# main.net
KiCad netlist of a schematic drawn in Altium Designer
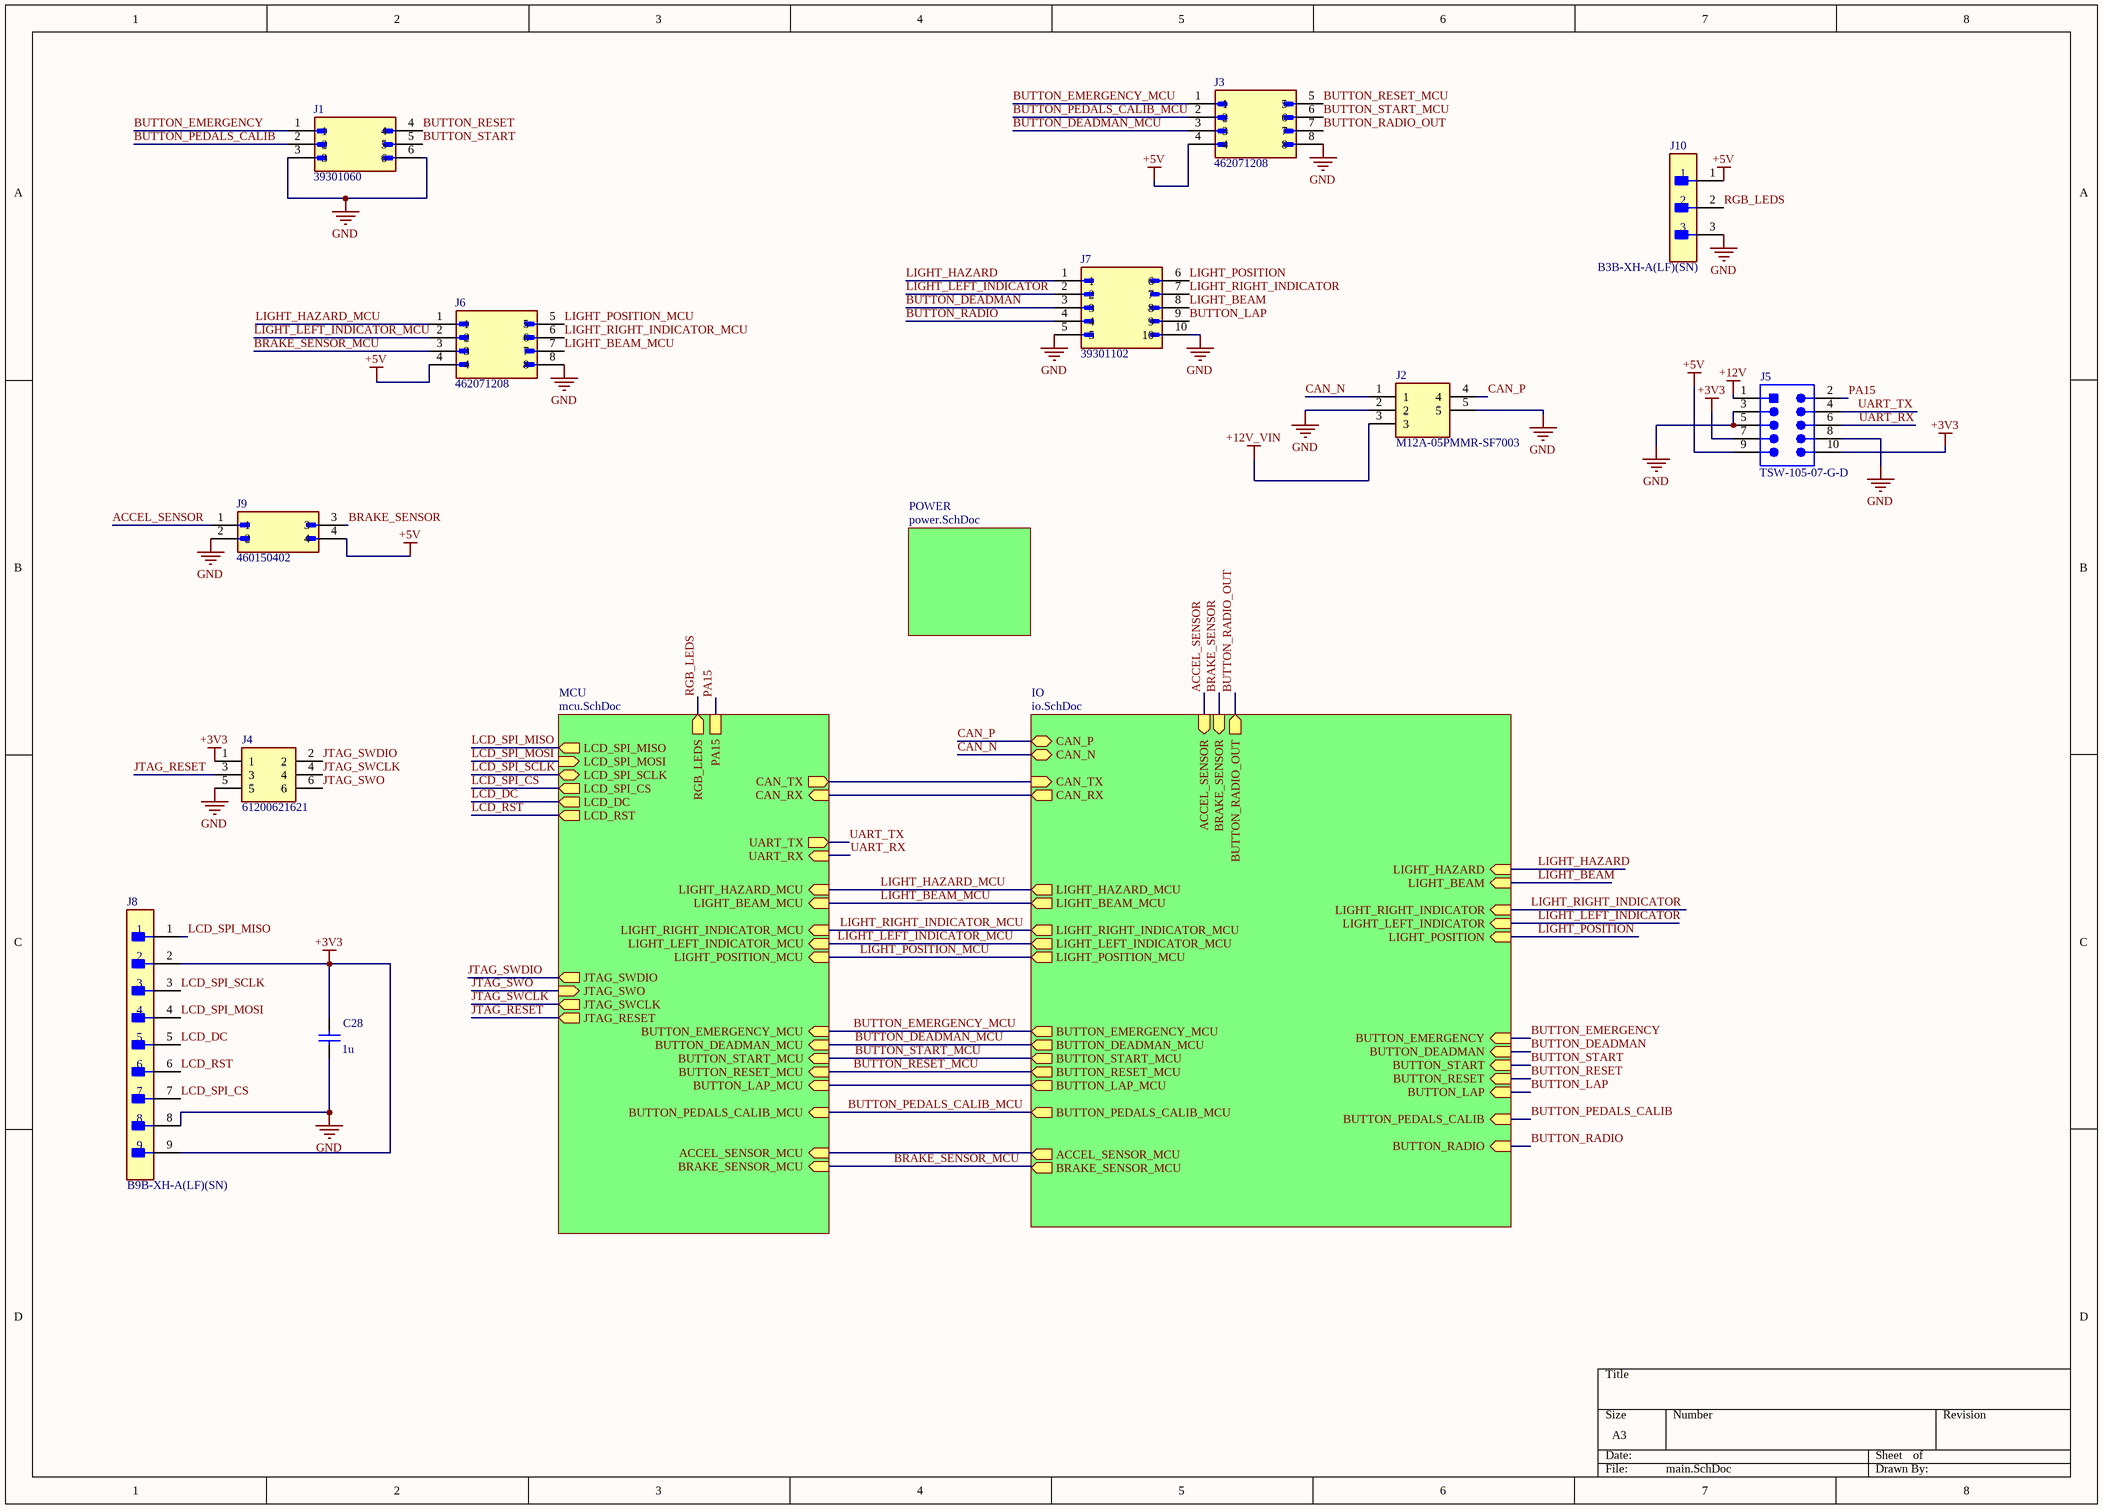
[diagram p0: main.SchDoc]

(export (version "E")
  (design (tool "Eeschema 10.0.6"))
  (components
    (comp (ref "C28")
      (value "1u")
      (footprint "CAPC1206(3216)150_L")
      (description "CAP 1.8uF 10V ±5% 1206 (3216 Metric) Thickness 1.45mm SMD")
      (fields (field (name "TOLERANCE") "Â±5%"))
      (libsource (lib "Altium Content Vault") (part "CAP"))
    )
    (comp (ref "J1")
      (value "39301060")
      (footprint "39301060")
      (description "Mini-Fit Jr. Through Hole PCB Header, Right Angle, 6 Contacts, 2 Rows, 4.2mm Pitch")
      (fields (field (name "MANUFACTURER") "Molex") (field (name "MANUFACTURER PART NUMBER") "39-30-1060"))
      (libsource (lib "HydrogreenLibrary") (part "39301060"))
    )
    (comp (ref "J2")
      (value "M12A-05PMMR-SF7003")
      (footprint "M12A05PMMRSF7003")
      (description "M12, A Code, 4A, 05 pins, Male Contact, Hexagonal, M12*1.0, PCB 90ø, Front Fastened, IP67")
      (fields
        (field (name "MOUSER PART NUMBER") "523-M12A05PMMRSF7003")
        (field (name "MANUFACTURER") "Amphenol LTW")
      )
      (libsource (lib "HydrogreenLibrary") (part "M12A-05PMMR-SF7003"))
    )
    (comp (ref "J3")
      (value "462071208")
      (footprint "462071208")
      (description "Mini-Fit Jr 46207 ROHS3Compliant Tin Solder Connector Header 100.0muin 2.54mum")
      (fields (field (name "MANUFACTURER") "Molex") (field (name "MANUFACTURER PART NUMBER") "46207-1208"))
      (libsource (lib "HydrogreenLibrary") (part "462071208"))
    )
    (comp (ref "J4")
      (value "61200621621")
      (footprint "61200621621")
      (description "Conn Shrouded Header (4 Sides) M 6 POS 2.54mm Solder ST Top Entry Thru-Hole Tray")
      (fields
        (field (name "MOUSER PART NUMBER") "710-61200621621")
        (field (name "MANUFACTURER") "Wurth Elektronik")
      )
      (libsource (lib "HydrogreenLibrary") (part "61200621621"))
    )
    (comp (ref "J5")
      (value "TSW-105-07-G-D")
      (footprint "SMTC-TSW-105-07-G-D_V")
      (fields (field (name "MANUFACTURER") "Samtec-Inc."))
      (libsource (lib "Altium Content Vault") (part "CN-2P-M-R10"))
    )
    (comp (ref "J6")
      (value "462071208")
      (footprint "462071208")
      (description "Mini-Fit Jr 46207 ROHS3Compliant Tin Solder Connector Header 100.0muin 2.54mum")
      (fields (field (name "MANUFACTURER") "Molex") (field (name "MANUFACTURER PART NUMBER") "46207-1208"))
      (libsource (lib "HydrogreenLibrary") (part "462071208"))
    )
    (comp (ref "J7")
      (value "39301102")
      (footprint "39301102")
      (libsource (lib "HydrogreenLibrary") (part "39301102"))
    )
    (comp (ref "J8")
      (value "B9B-XH-A(LF)(SN)")
      (footprint "FP-B9B-XH-A_LF_SN-MFG")
      (description "CONN HEADER VERT 9POS 2.5MM")
      (libsource (lib "Altium Content Vault") (part "dac6df820644cf490af5575b4ac23d9"))
    )
    (comp (ref "J9")
      (value "460150402")
      (footprint "460150402")
      (description "vert header, DR, 4w, tin, UL94V-0 ¦ Molex Incorporated 46015-0402")
      (fields (field (name "MF") "Molex") (field (name "MP") "46015-0402"))
      (libsource (lib "HydrogreenLibrary") (part "460150402"))
    )
    (comp (ref "J10")
      (value "B3B-XH-A(LF)(SN)")
      (footprint "FP-B3B-XH-A_LF_SN-MFG")
      (description "CONN HEADER VERT 3POS 2.5MM")
      (libsource (lib "Altium Content Vault") (part "0d3f023dd272f625e17a2be33dea85f"))
    )
  )
  (nets
    (net (code "1") (name "+3V3") (class "Default")
      (node (ref "C28") (pin "1") (pinfunction "1_1") (pintype "passive"))
      (node (ref "J4") (pin "1") (pinfunction "1_1") (pintype "passive"))
      (node (ref "J5") (pin "10") (pinfunction "10_10") (pintype "passive"))
      (node (ref "J5") (pin "7") (pinfunction "7_7") (pintype "passive"))
      (node (ref "J8") (pin "2") (pinfunction "2_2") (pintype "passive"))
      (node (ref "J8") (pin "9") (pinfunction "9_9") (pintype "passive"))
    )
    (net (code "2") (name "+5V") (class "Default")
      (node (ref "J10") (pin "1") (pinfunction "1_1") (pintype "passive"))
      (node (ref "J3") (pin "4") (pinfunction "4_4") (pintype "passive"))
      (node (ref "J5") (pin "9") (pinfunction "9_9") (pintype "passive"))
      (node (ref "J6") (pin "4") (pinfunction "4_4") (pintype "passive"))
      (node (ref "J9") (pin "4") (pinfunction "4_4") (pintype "passive"))
    )
    (net (code "3") (name "+12V") (class "Default")
      (node (ref "J5") (pin "1") (pinfunction "1_1") (pintype "passive"))
    )
    (net (code "4") (name "+12V_VIN") (class "Default")
      (node (ref "J2") (pin "3") (pinfunction "3_3") (pintype "passive"))
    )
    (net (code "5") (name "/ACCEL_SENSOR") (class "Default")
      (node (ref "J9") (pin "1") (pinfunction "1_1") (pintype "passive"))
    )
    (net (code "7") (name "/BRAKE_SENSOR") (class "Default")
      (node (ref "J9") (pin "3") (pinfunction "3_3") (pintype "passive"))
    )
    (net (code "8") (name "/BRAKE_SENSOR_MCU") (class "Default")
      (node (ref "J6") (pin "3") (pinfunction "3_3") (pintype "passive"))
    )
    (net (code "9") (name "/BUTTON_DEADMAN") (class "Default")
      (node (ref "J7") (pin "3") (pinfunction "3_3") (pintype "passive"))
    )
    (net (code "10") (name "/BUTTON_DEADMAN_MCU") (class "Default")
      (node (ref "J3") (pin "3") (pinfunction "3_3") (pintype "passive"))
    )
    (net (code "11") (name "/BUTTON_EMERGENCY") (class "Default")
      (node (ref "J1") (pin "1") (pinfunction "1_1") (pintype "passive"))
    )
    (net (code "12") (name "/BUTTON_EMERGENCY_MCU") (class "Default")
      (node (ref "J3") (pin "1") (pinfunction "1_1") (pintype "passive"))
    )
    (net (code "13") (name "/BUTTON_LAP") (class "Default")
      (node (ref "J7") (pin "9") (pinfunction "9_9") (pintype "passive"))
    )
    (net (code "15") (name "/BUTTON_PEDALS_CALIB") (class "Default")
      (node (ref "J1") (pin "2") (pinfunction "2_2") (pintype "passive"))
    )
    (net (code "16") (name "/BUTTON_PEDALS_CALIB_MCU") (class "Default")
      (node (ref "J3") (pin "2") (pinfunction "2_2") (pintype "passive"))
    )
    (net (code "17") (name "/BUTTON_RADIO") (class "Default")
      (node (ref "J7") (pin "4") (pinfunction "4_4") (pintype "passive"))
    )
    (net (code "18") (name "/BUTTON_RADIO_OUT") (class "Default")
      (node (ref "J3") (pin "7") (pinfunction "7_7") (pintype "passive"))
    )
    (net (code "19") (name "/BUTTON_RESET") (class "Default")
      (node (ref "J1") (pin "4") (pinfunction "4_4") (pintype "passive"))
    )
    (net (code "20") (name "/BUTTON_RESET_MCU") (class "Default")
      (node (ref "J3") (pin "5") (pinfunction "5_5") (pintype "passive"))
    )
    (net (code "21") (name "/BUTTON_START") (class "Default")
      (node (ref "J1") (pin "5") (pinfunction "5_5") (pintype "passive"))
    )
    (net (code "22") (name "/BUTTON_START_MCU") (class "Default")
      (node (ref "J3") (pin "6") (pinfunction "6_6") (pintype "passive"))
    )
    (net (code "23") (name "/CAN_N") (class "Default")
      (node (ref "J2") (pin "1") (pinfunction "1_1") (pintype "passive"))
    )
    (net (code "24") (name "/CAN_P") (class "Default")
      (node (ref "J2") (pin "4") (pinfunction "4_4") (pintype "passive"))
    )
    (net (code "27") (name "/JTAG_RESET") (class "Default")
      (node (ref "J4") (pin "3") (pinfunction "3_3") (pintype "passive"))
    )
    (net (code "28") (name "/JTAG_SWCLK") (class "Default")
      (node (ref "J4") (pin "4") (pinfunction "4_4") (pintype "passive"))
    )
    (net (code "29") (name "/JTAG_SWDIO") (class "Default")
      (node (ref "J4") (pin "2") (pinfunction "2_2") (pintype "passive"))
    )
    (net (code "30") (name "/JTAG_SWO") (class "Default")
      (node (ref "J4") (pin "6") (pinfunction "6_6") (pintype "passive"))
    )
    (net (code "31") (name "/LCD_DC") (class "Default")
      (node (ref "J8") (pin "5") (pinfunction "5_5") (pintype "passive"))
    )
    (net (code "32") (name "/LCD_RST") (class "Default")
      (node (ref "J8") (pin "6") (pinfunction "6_6") (pintype "passive"))
    )
    (net (code "33") (name "/LCD_SPI_CS") (class "Default")
      (node (ref "J8") (pin "7") (pinfunction "7_7") (pintype "passive"))
    )
    (net (code "34") (name "/LCD_SPI_MISO") (class "Default")
      (node (ref "J8") (pin "1") (pinfunction "1_1") (pintype "passive"))
    )
    (net (code "35") (name "/LCD_SPI_MOSI") (class "Default")
      (node (ref "J8") (pin "4") (pinfunction "4_4") (pintype "passive"))
    )
    (net (code "36") (name "/LCD_SPI_SCLK") (class "Default")
      (node (ref "J8") (pin "3") (pinfunction "3_3") (pintype "passive"))
    )
    (net (code "37") (name "/LIGHT_BEAM") (class "Default")
      (node (ref "J7") (pin "8") (pinfunction "8_8") (pintype "passive"))
    )
    (net (code "38") (name "/LIGHT_BEAM_MCU") (class "Default")
      (node (ref "J6") (pin "7") (pinfunction "7_7") (pintype "passive"))
    )
    (net (code "39") (name "/LIGHT_HAZARD") (class "Default")
      (node (ref "J7") (pin "1") (pinfunction "1_1") (pintype "passive"))
    )
    (net (code "40") (name "/LIGHT_HAZARD_MCU") (class "Default")
      (node (ref "J6") (pin "1") (pinfunction "1_1") (pintype "passive"))
    )
    (net (code "41") (name "/LIGHT_LEFT_INDICATOR") (class "Default")
      (node (ref "J7") (pin "2") (pinfunction "2_2") (pintype "passive"))
    )
    (net (code "42") (name "/LIGHT_LEFT_INDICATOR_MCU") (class "Default")
      (node (ref "J6") (pin "2") (pinfunction "2_2") (pintype "passive"))
    )
    (net (code "43") (name "/LIGHT_POSITION") (class "Default")
      (node (ref "J7") (pin "6") (pinfunction "6_6") (pintype "passive"))
    )
    (net (code "44") (name "/LIGHT_POSITION_MCU") (class "Default")
      (node (ref "J6") (pin "5") (pinfunction "5_5") (pintype "passive"))
    )
    (net (code "45") (name "/LIGHT_RIGHT_INDICATOR") (class "Default")
      (node (ref "J7") (pin "7") (pinfunction "7_7") (pintype "passive"))
    )
    (net (code "46") (name "/LIGHT_RIGHT_INDICATOR_MCU") (class "Default")
      (node (ref "J6") (pin "6") (pinfunction "6_6") (pintype "passive"))
    )
    (net (code "47") (name "/PA15") (class "Default")
      (node (ref "J5") (pin "2") (pinfunction "2_2") (pintype "passive"))
    )
    (net (code "48") (name "/RGB_LEDS") (class "Default")
      (node (ref "J10") (pin "2") (pinfunction "2_2") (pintype "passive"))
    )
    (net (code "49") (name "/UART_RX") (class "Default")
      (node (ref "J5") (pin "6") (pinfunction "6_6") (pintype "passive"))
    )
    (net (code "50") (name "/UART_TX") (class "Default")
      (node (ref "J5") (pin "4") (pinfunction "4_4") (pintype "passive"))
    )
    (net (code "51") (name "GND") (class "Default")
      (node (ref "C28") (pin "2") (pinfunction "2_2") (pintype "passive"))
      (node (ref "J1") (pin "3") (pinfunction "3_3") (pintype "passive"))
      (node (ref "J1") (pin "6") (pinfunction "6_6") (pintype "passive"))
      (node (ref "J10") (pin "3") (pinfunction "3_3") (pintype "passive"))
      (node (ref "J2") (pin "2") (pinfunction "2_2") (pintype "passive"))
      (node (ref "J2") (pin "5") (pinfunction "5_5") (pintype "passive"))
      (node (ref "J3") (pin "8") (pinfunction "8_8") (pintype "passive"))
      (node (ref "J4") (pin "5") (pinfunction "5_5") (pintype "passive"))
      (node (ref "J5") (pin "3") (pinfunction "3_3") (pintype "passive"))
      (node (ref "J5") (pin "5") (pinfunction "5_5") (pintype "passive"))
      (node (ref "J5") (pin "8") (pinfunction "8_8") (pintype "passive"))
      (node (ref "J6") (pin "8") (pinfunction "8_8") (pintype "passive"))
      (node (ref "J7") (pin "10") (pinfunction "10_10") (pintype "passive"))
      (node (ref "J7") (pin "5") (pinfunction "5_5") (pintype "passive"))
      (node (ref "J8") (pin "8") (pinfunction "8_8") (pintype "passive"))
      (node (ref "J9") (pin "2") (pinfunction "2_2") (pintype "passive"))
    )
  )
)
